# driver.net
KiCad netlist of a schematic drawn in EAGLE
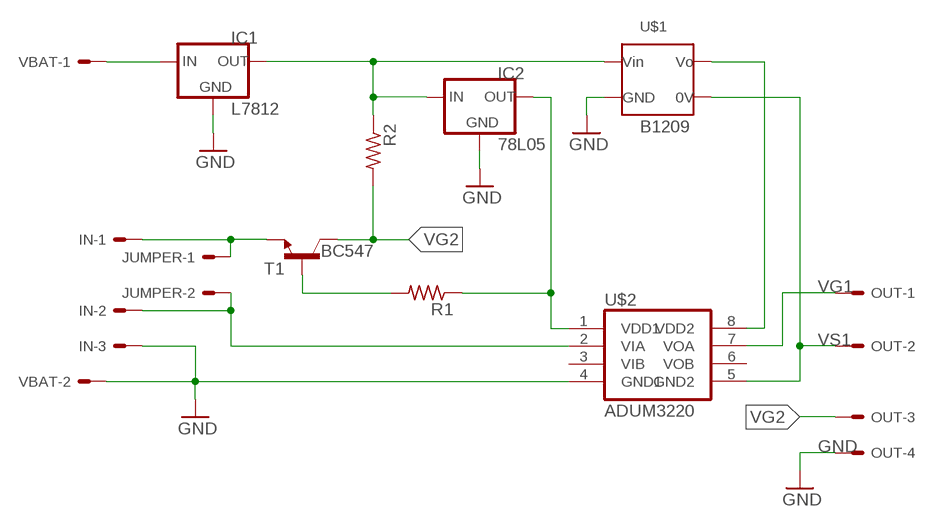
[diagram p0: schematic, sheet 1]

(export (version "E")
  (design (tool "Eeschema 10.0.6"))
  (components
    (comp (ref "IC1")
      (value "L7812")
      (footprint "eagle-import:78XXL")
      (libsource (lib "eagle-import") (part "78XXL"))
    )
    (comp (ref "IC2")
      (value "78L05")
      (footprint "eagle-import:78LXX")
      (libsource (lib "eagle-import") (part "78LXX"))
    )
    (comp (ref "IN")
      (value "22-23-2031")
      (footprint "eagle-import:22-23-2031")
      (fields (field (name "MF") "MOLEX"))
      (libsource (lib "eagle-import") (part "22-23-2031"))
    )
    (comp (ref "JUMPER")
      (value "22-23-2021")
      (footprint "eagle-import:22-23-2021")
      (fields (field (name "MF") "MOLEX"))
      (libsource (lib "eagle-import") (part "22-23-2021"))
    )
    (comp (ref "OUT")
      (value "22-23-2041")
      (footprint "eagle-import:22-23-2041")
      (fields (field (name "MF") "MOLEX"))
      (libsource (lib "eagle-import") (part "22-23-2041"))
    )
    (comp (ref "R1")
      (value "R-US_0204/7")
      (footprint "eagle-import:0204_7")
      (libsource (lib "eagle-import") (part "R-US_0204/7"))
    )
    (comp (ref "R2")
      (value "R-US_0204/7")
      (footprint "eagle-import:0204_7")
      (libsource (lib "eagle-import") (part "R-US_0204/7"))
    )
    (comp (ref "T1")
      (value "BC547")
      (footprint "eagle-import:TO92")
      (libsource (lib "eagle-import") (part "BC547"))
    )
    (comp (ref "U$1")
      (value "B1209")
      (footprint "eagle-import:22-23-2041")
      (libsource (lib "eagle-import") (part "B1209"))
    )
    (comp (ref "U$2")
      (value "ADUM3220")
      (footprint "eagle-import:SO8")
      (libsource (lib "eagle-import") (part "ADUM3220"))
    )
    (comp (ref "VBAT")
      (value "22-23-2021")
      (footprint "eagle-import:22-23-2021")
      (fields (field (name "MF") "MOLEX"))
      (libsource (lib "eagle-import") (part "22-23-2021"))
    )
  )
  (nets
    (net (code "1") (name "/VG1") (class "Default")
      (node (ref "OUT") (pin "1") (pinfunction "S_1") (pintype "passive"))
      (node (ref "U$2") (pin "7") (pinfunction "VOA_7") (pintype "output"))
    )
    (net (code "2") (name "/VS1") (class "Default")
      (node (ref "OUT") (pin "2") (pinfunction "S_2") (pintype "passive"))
      (node (ref "U$1") (pin "3") (pinfunction "0V_3") (pintype "passive"))
      (node (ref "U$2") (pin "5") (pinfunction "GND2_5") (pintype "output"))
    )
    (net (code "3") (name "GND") (class "Default")
      (node (ref "IC1") (pin "GND") (pinfunction "GND_GND") (pintype "input"))
      (node (ref "IC2") (pin "GND") (pinfunction "GND_GND") (pintype "input"))
      (node (ref "IN") (pin "3") (pinfunction "S_3") (pintype "passive"))
      (node (ref "OUT") (pin "4") (pinfunction "S_4") (pintype "passive"))
      (node (ref "U$1") (pin "1") (pinfunction "GND_1") (pintype "passive"))
      (node (ref "U$2") (pin "4") (pinfunction "GND1_4") (pintype "input"))
      (node (ref "VBAT") (pin "2") (pinfunction "S_2") (pintype "passive"))
    )
    (net (code "4") (name "Net-(INA-S)") (class "Default")
      (node (ref "IN") (pin "1") (pinfunction "S_1") (pintype "passive"))
      (node (ref "JUMPER") (pin "1") (pinfunction "S_1") (pintype "passive"))
      (node (ref "T1") (pin "1") (pinfunction "E_1") (pintype "passive"))
    )
    (net (code "5") (name "Net-(INB-S)") (class "Default")
      (node (ref "IN") (pin "2") (pinfunction "S_2") (pintype "passive"))
      (node (ref "JUMPER") (pin "2") (pinfunction "S_2") (pintype "passive"))
      (node (ref "U$2") (pin "2") (pinfunction "VIA_2") (pintype "input"))
    )
    (net (code "6") (name "Net-(T1-B)") (class "Default")
      (node (ref "R1") (pin "2") (pinfunction "2_2") (pintype "passive"))
      (node (ref "T1") (pin "2") (pinfunction "B_2") (pintype "passive"))
    )
    (net (code "7") (name "Net-(U$1-VIN)") (class "Default")
      (node (ref "IC1") (pin "OUT") (pinfunction "OUT_OUT") (pintype "passive"))
      (node (ref "IC2") (pin "IN") (pinfunction "IN_IN") (pintype "input"))
      (node (ref "R2") (pin "1") (pinfunction "1_1") (pintype "passive"))
      (node (ref "U$1") (pin "2") (pinfunction "VIN_2") (pintype "passive"))
    )
    (net (code "8") (name "Net-(U$1-VO)") (class "Default")
      (node (ref "U$1") (pin "4") (pinfunction "VO_4") (pintype "passive"))
      (node (ref "U$2") (pin "8") (pinfunction "VDD2_8") (pintype "output"))
    )
    (net (code "9") (name "Net-(U$2-VDD1)") (class "Default")
      (node (ref "IC2") (pin "OUT") (pinfunction "OUT_OUT") (pintype "passive"))
      (node (ref "R1") (pin "1") (pinfunction "1_1") (pintype "passive"))
      (node (ref "U$2") (pin "1") (pinfunction "VDD1_1") (pintype "input"))
    )
    (net (code "10") (name "Net-(VBATA-S)") (class "Default")
      (node (ref "IC1") (pin "IN") (pinfunction "IN_IN") (pintype "input"))
      (node (ref "VBAT") (pin "1") (pinfunction "S_1") (pintype "passive"))
    )
    (net (code "11") (name "VG2") (class "Default")
      (node (ref "OUT") (pin "3") (pinfunction "S_3") (pintype "passive"))
      (node (ref "R2") (pin "2") (pinfunction "2_2") (pintype "passive"))
      (node (ref "T1") (pin "3") (pinfunction "C_3") (pintype "passive"))
    )
    (net (code "12") (name "unconnected-(U$2-VIB-Pad3)") (class "Default")
      (node (ref "U$2") (pin "3") (pinfunction "VIB_3") (pintype "input"))
    )
    (net (code "13") (name "unconnected-(U$2-VOB-Pad6)") (class "Default")
      (node (ref "U$2") (pin "6") (pinfunction "VOB_6") (pintype "output"))
    )
  )
)
